# STM32WL_QFN48_4Layers_Ref_Board.net
KiCad netlist of a schematic drawn in Altium Designer
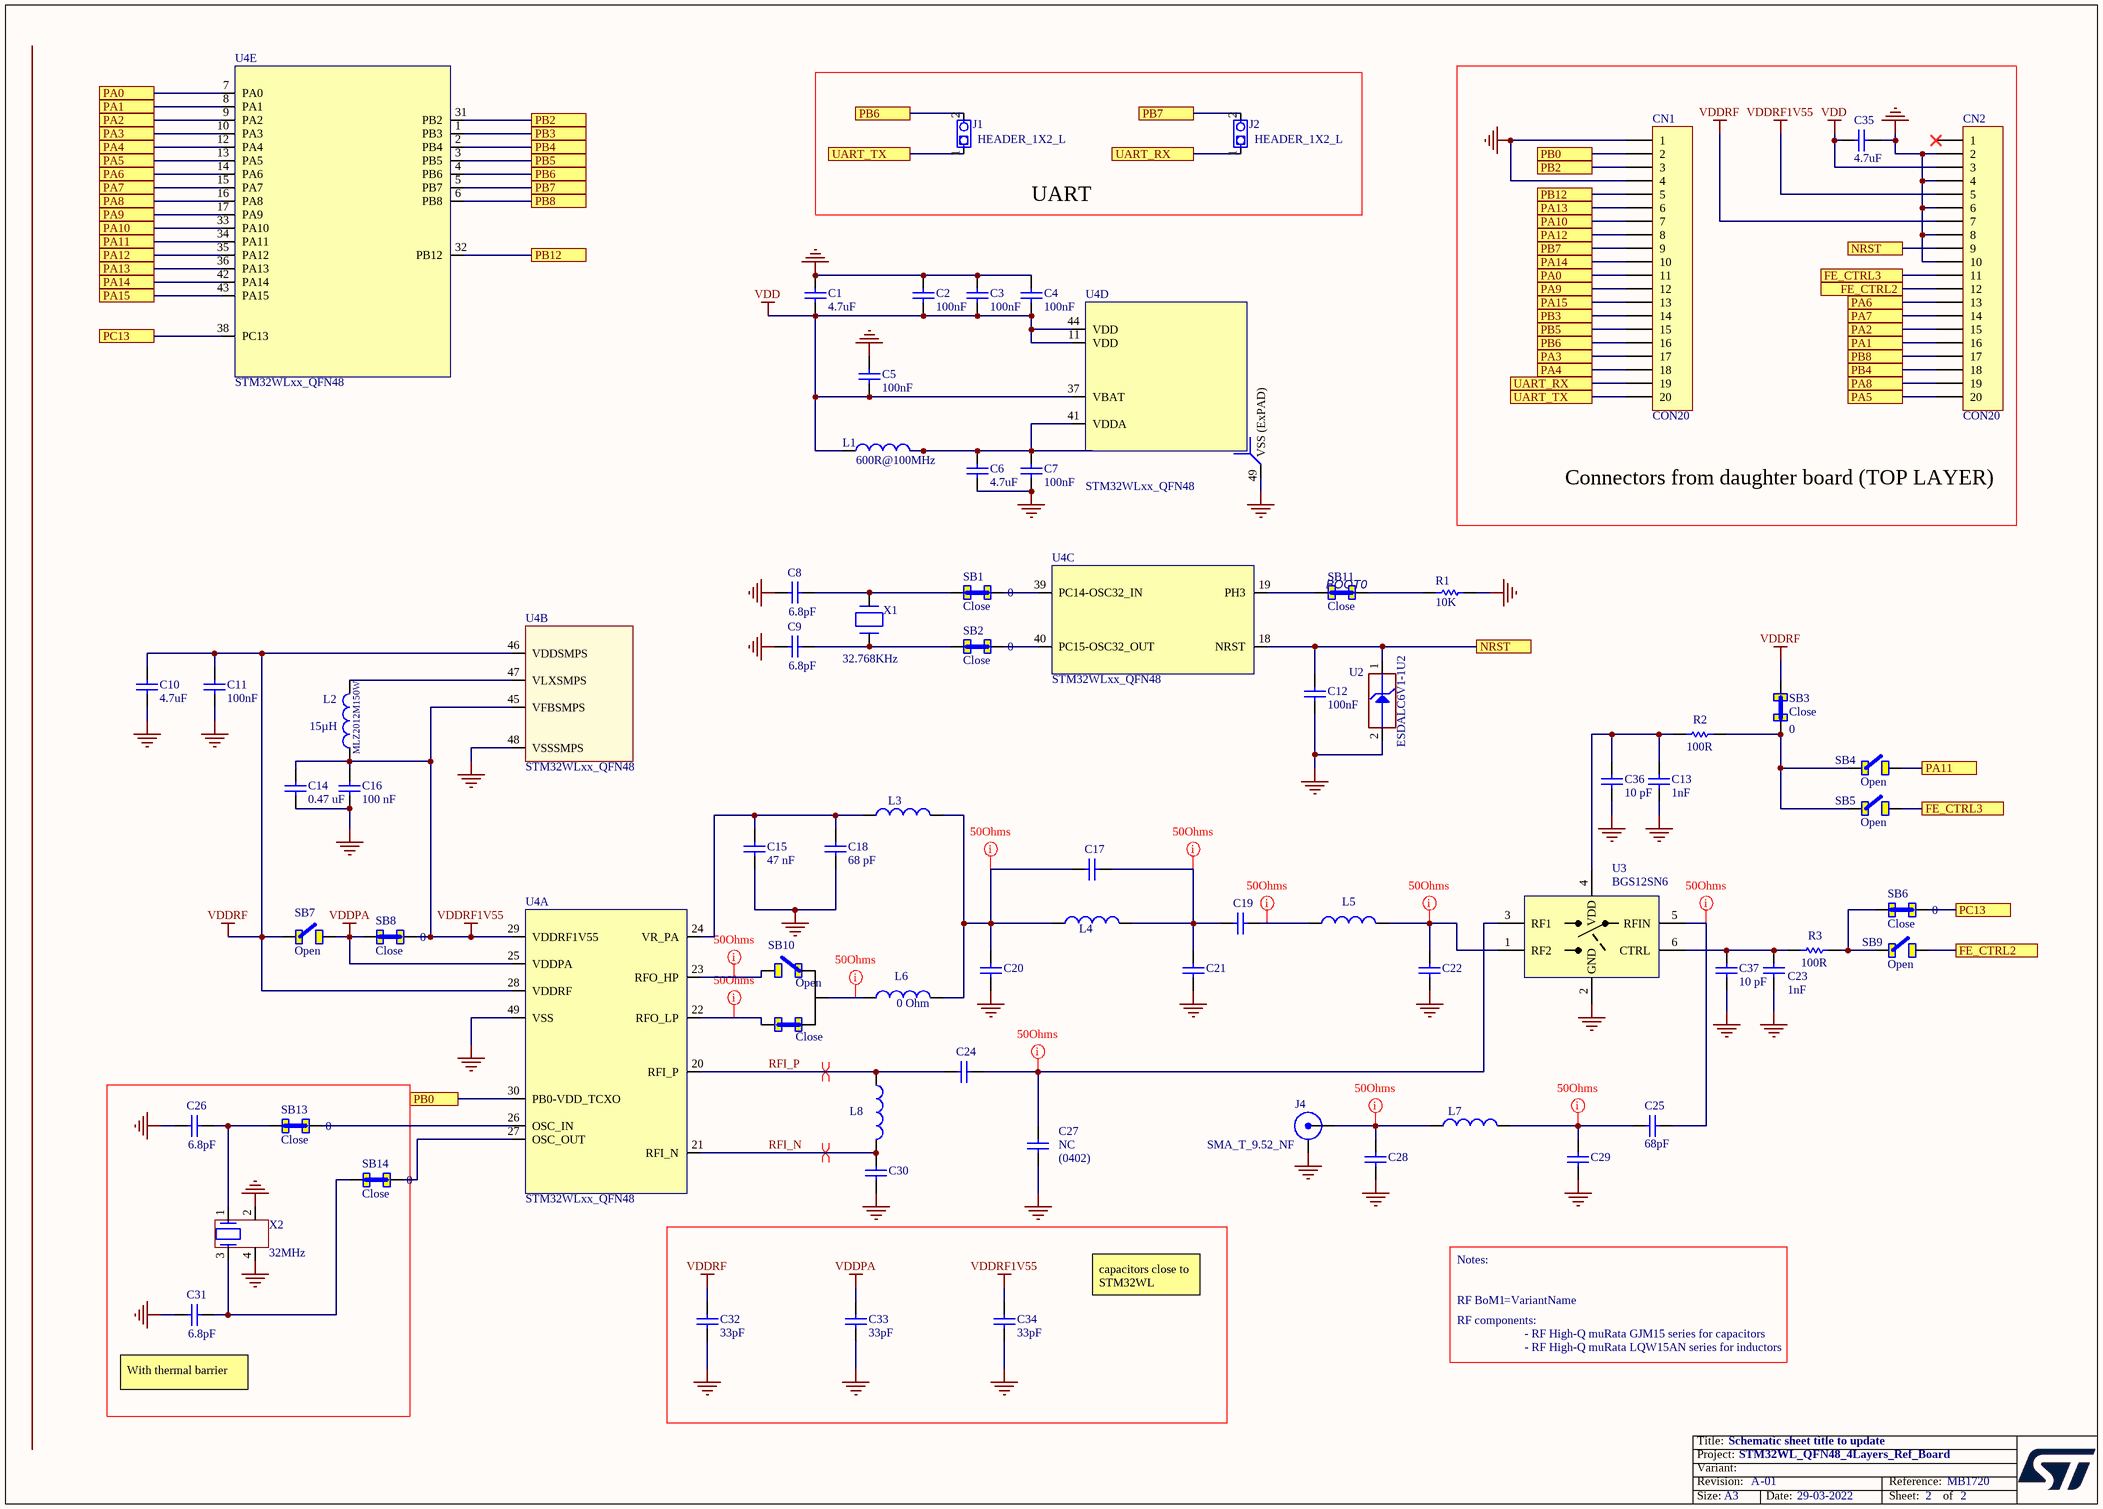
[diagram p0: STM32WL_QFN48_4Layers_Ref_Board.SchDoc]

(export (version "E")
  (design (tool "Eeschema 10.0.6"))
  (components
    (comp (ref "C1")
      (value "4.7uF")
      (footprint "CAPC1608X09N")
      (description "Capacitor, MLCC, 4.7uF, 16V, X5R, 10%, 0603, T=0.8mm")
      (fields
        (field (name "MANUFACTURER_PART_NUMBER") "CC0603KRX5R7BB475")
        (field (name "MANUFACTURER") "YAGEO")
      )
      (libsource (lib "MCD_PARTS_database") (part "Capacitor"))
    )
    (comp (ref "C2")
      (value "100nF")
      (footprint "CAPC1005X06N")
      (description "Capacitor, MLCC, 100nF, 16V, X7R, 10%, 0402, T=0,5mm")
      (fields
        (field (name "MANUFACTURER_PART_NUMBER") "CC0402KRX7R7BB104")
        (field (name "MANUFACTURER") "YAGEO")
      )
      (libsource (lib "MCD_PARTS_database") (part "Capacitor"))
    )
    (comp (ref "C3")
      (value "100nF")
      (footprint "CAPC1005X06N")
      (description "Capacitor, MLCC, 100nF, 16V, X7R, 10%, 0402, T=0,5mm")
      (fields
        (field (name "MANUFACTURER_PART_NUMBER") "CC0402KRX7R7BB104")
        (field (name "MANUFACTURER") "YAGEO")
      )
      (libsource (lib "MCD_PARTS_database") (part "Capacitor"))
    )
    (comp (ref "C4")
      (value "100nF")
      (footprint "CAPC1005X06N")
      (description "Capacitor, MLCC, 100nF, 16V, X7R, 10%, 0402, T=0,5mm")
      (fields
        (field (name "MANUFACTURER_PART_NUMBER") "CC0402KRX7R7BB104")
        (field (name "MANUFACTURER") "YAGEO")
      )
      (libsource (lib "MCD_PARTS_database") (part "Capacitor"))
    )
    (comp (ref "C5")
      (value "100nF")
      (footprint "CAPC1005X06N")
      (description "Capacitor, MLCC, 100nF, 16V, X7R, 10%, 0402, T=0,5mm")
      (fields
        (field (name "MANUFACTURER_PART_NUMBER") "CC0402KRX7R7BB104")
        (field (name "MANUFACTURER") "YAGEO")
      )
      (libsource (lib "MCD_PARTS_database") (part "Capacitor"))
    )
    (comp (ref "C6")
      (value "4.7uF")
      (footprint "CAPC1608X09N")
      (description "Capacitor, MLCC, 4.7uF, 16V, X5R, 10%, 0603, T=0.8mm")
      (fields
        (field (name "MANUFACTURER_PART_NUMBER") "CC0603KRX5R7BB475")
        (field (name "MANUFACTURER") "YAGEO")
      )
      (libsource (lib "MCD_PARTS_database") (part "Capacitor"))
    )
    (comp (ref "C7")
      (value "100nF")
      (footprint "CAPC1005X06N")
      (description "Capacitor, MLCC, 100nF, 16V, X7R, 10%, 0402, T=0,5mm")
      (fields
        (field (name "MANUFACTURER_PART_NUMBER") "CC0402KRX7R7BB104")
        (field (name "MANUFACTURER") "YAGEO")
      )
      (libsource (lib "MCD_PARTS_database") (part "Capacitor"))
    )
    (comp (ref "C8")
      (value "6.8pF")
      (footprint "CAPC1005X06N")
      (description "Capacitor, MLCC, 6.8pF, 50V, NPO, +-0.1pF, 0402, T=0.5mm")
      (fields
        (field (name "MANUFACTURER_PART_NUMBER") "GRM1555C1H6R8BA01")
        (field (name "MANUFACTURER") "MURATA")
      )
      (libsource (lib "MCD_PARTS_database") (part "Capacitor"))
    )
    (comp (ref "C9")
      (value "6.8pF")
      (footprint "CAPC1005X06N")
      (description "Capacitor, MLCC, 6.8pF, 50V, NPO, +-0.1pF, 0402, T=0.5mm")
      (fields
        (field (name "MANUFACTURER_PART_NUMBER") "GRM1555C1H6R8BA01")
        (field (name "MANUFACTURER") "MURATA")
      )
      (libsource (lib "MCD_PARTS_database") (part "Capacitor"))
    )
    (comp (ref "C10")
      (value "4.7uF")
      (footprint "CAPC1608X09N")
      (description "Capacitor, MLCC, 4.7uF, 16V, X5R, 10%, 0603, T=0.8mm")
      (fields
        (field (name "MANUFACTURER_PART_NUMBER") "CC0603KRX5R7BB475")
        (field (name "MANUFACTURER") "YAGEO")
      )
      (libsource (lib "MCD_PARTS_database") (part "Capacitor"))
    )
    (comp (ref "C11")
      (value "100nF")
      (footprint "CAPC1005X06N")
      (description "Capacitor, MLCC, 100nF, 16V, X7R, 10%, 0402, T=0,5mm")
      (fields
        (field (name "MANUFACTURER_PART_NUMBER") "CC0402KRX7R7BB104")
        (field (name "MANUFACTURER") "YAGEO")
      )
      (libsource (lib "MCD_PARTS_database") (part "Capacitor"))
    )
    (comp (ref "C12")
      (value "100nF")
      (footprint "CAPC1005X06N")
      (description "Capacitor, MLCC, 100nF, 16V, X7R, 10%, 0402, T=0,5mm")
      (fields
        (field (name "MANUFACTURER_PART_NUMBER") "CC0402KRX7R7BB104")
        (field (name "MANUFACTURER") "YAGEO")
      )
      (libsource (lib "MCD_PARTS_database") (part "Capacitor"))
    )
    (comp (ref "C13")
      (value "1nF")
      (footprint "CAPC1005X06N")
      (description "Capacitor, MLCC, 1nF, 16V, X7R, 10%, 0402, T=0.5mm")
      (fields
        (field (name "MANUFACTURER_PART_NUMBER") "CC0402KRX7R7BB102")
        (field (name "MANUFACTURER") "YAGEO")
      )
      (libsource (lib "MCD_PARTS_database") (part "Capacitor"))
    )
    (comp (ref "C14")
      (value "0.47 uF")
      (footprint "CAPC1608X09N")
      (description "Capacitor, MLCC, 4.7 uF, 16V, X5R, 10%, 0603, T=0.8mm")
      (fields
        (field (name "MANUFACTURER_PART_NUMBER") "CC0603KRX5R7BB474")
        (field (name "MANUFACTURER") "YAGEO")
      )
      (libsource (lib "MCD_PARTS_database") (part "Capacitor"))
    )
    (comp (ref "C15")
      (value "47 nF")
      (footprint "0402")
      (description "Capacitor, MLCC,47nF, 16V, X7R, 10%, 0402, T=0.5mm")
      (fields
        (field (name "MANUFACTURER_PART_NUMBER") "GCM155R71E473KA55")
        (field (name "MANUFACTURER") "MURATA")
      )
      (libsource (lib "MB1791") (part "Capacitor"))
    )
    (comp (ref "C16")
      (value "100 nF")
      (footprint "CAPC1608X09N")
      (description "Capacitor, MLCC, 100 nF, 16V, X5R, 10%, 0603, T=0.8mm")
      (fields (field (name "MANUFACTURER") "YAGEO"))
      (libsource (lib "MCD_PARTS_database") (part "Capacitor"))
    )
    (comp (ref "C17")
      (value "~")
      (footprint "CAPC1005X06N")
      (description "RF Capacitor")
      (libsource (lib "MCD_PARTS_database") (part "Capacitor"))
    )
    (comp (ref "C18")
      (value "68 pF")
      (footprint "0402")
      (description "Capacitor, MLCC,68pF, 50V, C0G, 1%, 0402, T=0.5mm")
      (fields
        (field (name "MANUFACTURER_PART_NUMBER") "GCM1555C1H680JA16")
        (field (name "MANUFACTURER") "MURATA")
      )
      (libsource (lib "MB1791") (part "Capacitor"))
    )
    (comp (ref "C19")
      (value "~")
      (footprint "CAPC1005X06N")
      (description "RF Capacitor")
      (libsource (lib "MCD_PARTS_database") (part "Capacitor"))
    )
    (comp (ref "C20")
      (value "~")
      (footprint "CAPC1005X06N")
      (description "RF Capacitor")
      (fields (field (name "MANUFACTURER_PART_NUMBER") "Not Connected"))
      (libsource (lib "MCD_PARTS_database") (part "Capacitor"))
    )
    (comp (ref "C21")
      (value "~")
      (footprint "CAPC1005X06N")
      (description "RF Capacitor")
      (libsource (lib "MCD_PARTS_database") (part "Capacitor"))
    )
    (comp (ref "C22")
      (value "~")
      (footprint "CAPC1005X06N")
      (description "RF Capacitor")
      (libsource (lib "MCD_PARTS_database") (part "Capacitor"))
    )
    (comp (ref "C23")
      (value "1nF")
      (footprint "CAPC1005X06N")
      (description "Capacitor, MLCC, 1nF, 16V, X7R, 10%, 0402, T=0.5mm")
      (fields
        (field (name "MANUFACTURER_PART_NUMBER") "CC0402KRX7R7BB102")
        (field (name "MANUFACTURER") "YAGEO")
      )
      (libsource (lib "MCD_PARTS_database") (part "Capacitor"))
    )
    (comp (ref "C24")
      (value "~")
      (footprint "CAPC1005X06N")
      (description "RF Capacitor")
      (libsource (lib "MCD_PARTS_database") (part "Capacitor"))
    )
    (comp (ref "C25")
      (value "68pF")
      (footprint "CAPC1005X06N")
      (description "RF Capacitor")
      (fields
        (field (name "MANUFACTURER_PART_NUMBER") "GRM1555C1HR68WB01D")
        (field (name "MANUFACTURER") "Murata")
      )
      (libsource (lib "MCD_PARTS_database") (part "Capacitor"))
    )
    (comp (ref "C26")
      (value "6.8pF")
      (footprint "CAPC1005X06N")
      (description "Capacitor, MLCC, 6.8pF, 50V, NPO, +-0.1pF, 0402, T=0.5mm")
      (fields
        (field (name "MANUFACTURER_PART_NUMBER") "GRM1555C1H6R8BA01")
        (field (name "MANUFACTURER") "MURATA")
      )
      (libsource (lib "MCD_PARTS_database") (part "Capacitor"))
    )
    (comp (ref "C27")
      (value "NC")
      (footprint "CAPC1005X06N")
      (description "RF Capacitor")
      (fields (field (name "MANUFACTURER") "MURATA") (field (name "ALTIUM_VALUE") "(0402)"))
      (libsource (lib "MCD_PARTS_database") (part "Capacitor"))
    )
    (comp (ref "C28")
      (value "~")
      (footprint "CAPC1005X06N - duplicate - duplicate")
      (description "RF Capacitor")
      (libsource (lib "MBxx") (part "Capacitor"))
    )
    (comp (ref "C29")
      (value "~")
      (footprint "CAPC1005X06N - duplicate - duplicate")
      (description "RF Capacitor")
      (libsource (lib "MCD_PARTS_database") (part "Capacitor"))
    )
    (comp (ref "C30")
      (value "~")
      (footprint "CAPC1005X06N")
      (description "RF Capacitor")
      (libsource (lib "MCD_PARTS_database") (part "Capacitor"))
    )
    (comp (ref "C31")
      (value "6.8pF")
      (footprint "CAPC1005X06N")
      (description "Capacitor, MLCC, 6.8pF, 50V, NPO, +-0.1pF, 0402, T=0.5mm")
      (fields
        (field (name "MANUFACTURER_PART_NUMBER") "GRM1555C1H6R8BA01")
        (field (name "MANUFACTURER") "MURATA")
      )
      (libsource (lib "MCD_PARTS_database") (part "Capacitor"))
    )
    (comp (ref "C32")
      (value "33pF")
      (footprint "CAPC1005X06N")
      (description "Capacitor, MLCC, 33pF, 50V, NPO, 2%, 0402, T=0,5mm")
      (fields
        (field (name "MANUFACTURER_PART_NUMBER") "GRM1555C1H330GA01")
        (field (name "MANUFACTURER") "MURATA")
      )
      (libsource (lib "MCD_PARTS_database") (part "Capacitor"))
    )
    (comp (ref "C33")
      (value "33pF")
      (footprint "CAPC1005X06N")
      (description "Capacitor, MLCC, 33pF, 50V, NPO, 2%, 0402, T=0,5mm")
      (fields
        (field (name "MANUFACTURER_PART_NUMBER") "GRM1555C1H330GA01")
        (field (name "MANUFACTURER") "MURATA")
      )
      (libsource (lib "MCD_PARTS_database") (part "Capacitor"))
    )
    (comp (ref "C34")
      (value "33pF")
      (footprint "CAPC1005X06N")
      (description "Capacitor, MLCC, 33pF, 50V, NPO, 2%, 0402, T=0,5mm")
      (fields
        (field (name "MANUFACTURER_PART_NUMBER") "GRM1555C1H330GA01")
        (field (name "MANUFACTURER") "MURATA")
      )
      (libsource (lib "MCD_PARTS_database") (part "Capacitor"))
    )
    (comp (ref "C35")
      (value "4.7uF")
      (footprint "CAPC1608X09N")
      (description "Capacitor, MLCC, 4.7uF, 16V, X5R, 10%, 0603, T=0.8mm")
      (fields
        (field (name "MANUFACTURER_PART_NUMBER") "CC0603KRX5R7BB475")
        (field (name "MANUFACTURER") "YAGEO")
      )
      (libsource (lib "MCD_PARTS_database") (part "Capacitor"))
    )
    (comp (ref "C36")
      (value "10 pF")
      (footprint "CAPC1005X06N")
      (description "10pF ±1% 50V Ceramic Capacitor C0G, NP0 0402 (1005 Metric)")
      (fields
        (field (name "MANUFACTURER_PART_NUMBER") "GJM1555C1H100FB01D")
        (field (name "MANUFACTURER") "MURATA")
      )
      (libsource (lib "MB1720") (part "Capa_0402"))
    )
    (comp (ref "C37")
      (value "10 pF")
      (footprint "CAPC1005X06N")
      (description "10pF ±1% 50V Ceramic Capacitor C0G, NP0 0402 (1005 Metric)")
      (fields
        (field (name "MANUFACTURER_PART_NUMBER") "GJM1555C1H100FB01D")
        (field (name "MANUFACTURER") "MURATA")
      )
      (libsource (lib "MB1720") (part "Capa_0402"))
    )
    (comp (ref "CN1")
      (value "CON20")
      (footprint "CO_SAMTEC_TSW-120-07-x-S")
      (description "Connector right-angle, pitch 2.54mm, 20 contacts")
      (fields
        (field (name "MANUFACTURER") "SAMTEC")
        (field (name "MANUFACTURER_PART_NUMBER") "TSW-120-07-L-S")
      )
      (libsource (lib "Connector") (part "CON20"))
    )
    (comp (ref "CN2")
      (value "CON20")
      (footprint "CO_SAMTEC_TSW-120-07-x-S")
      (description "Connector right-angle, pitch 2.54mm, 20 contacts")
      (fields
        (field (name "MANUFACTURER") "SAMTEC")
        (field (name "MANUFACTURER_PART_NUMBER") "TSW-120-07-L-S")
      )
      (libsource (lib "Connector") (part "CON20"))
    )
    (comp (ref "J1")
      (value "HEADER_1X2_L")
      (footprint "CO_MOLEX_22-03-2021")
      (description "Header 1x2 Through hole 2.54mm")
      (fields (field (name "MANUFACTURER") "MOLEX") (field (name "MANUFACTURER_PART_NUMBER") "22-03-2021"))
      (libsource (lib "Connector") (part "HEADER_1X2_L"))
    )
    (comp (ref "J2")
      (value "HEADER_1X2_L")
      (footprint "CO_MOLEX_22-03-2021")
      (description "Header 1x2 Through hole 2.54mm")
      (fields (field (name "MANUFACTURER") "MOLEX") (field (name "MANUFACTURER_PART_NUMBER") "22-03-2021"))
      (libsource (lib "Connector") (part "HEADER_1X2_L"))
    )
    (comp (ref "J4")
      (value "SMA_T_9.52_NF")
      (footprint "CO_SAMTEC_SMA-J-P-ST-EMI")
      (description "SMA Jack, Edge Mount, 50 Ohms")
      (fields
        (field (name "MANUFACTURER") "SAMTEC")
        (field (name "MANUFACTURER_PART_NUMBER") "SMA-J-P-H-ST-EM1")
      )
      (libsource (lib "STM32WB55_DB_CSP100_P") (part "SMA_T_9.52_NF"))
    )
    (comp (ref "L1")
      (value "600R@100MHz")
      (footprint "INDC1608X95N")
      (description "SMD Chip ferrite bead, 600R@100MHz +/-25%, 350mA, 500mohm DC, 0603, T=0.8mm")
      (fields
        (field (name "MANUFACTURER_PART_NUMBER") "FCM1608KF-601T03")
        (field (name "MANUFACTURER") "TAI-TECH")
      )
      (libsource (lib "MCD_PARTS_database") (part "BEAD"))
    )
    (comp (ref "L2")
      (value "15µH")
      (footprint "INDC2012X13N")
      (description "MLZ2012 Multilayer Shielded Inductor 15µH, ±5%")
      (fields (field (name "MANUFACTURER_PART_NUMBER") "MLZ2012M150W") (field (name "MANUFACTURER") "TDK"))
      (libsource (lib "") (part "Inductor_1"))
    )
    (comp (ref "L3")
      (value "~")
      (footprint "IND_MURATA_LQW15A")
      (description "RF Inductor")
      (fields (field (name "MANUFACTURER") "MURATA"))
      (libsource (lib "MCD_PARTS_database") (part "Inductor"))
    )
    (comp (ref "L4")
      (value "~")
      (footprint "IND_MURATA_LQW15A")
      (description "RF Inductor")
      (libsource (lib "") (part "Inductor_1"))
    )
    (comp (ref "L5")
      (value "~")
      (footprint "IND_MURATA_LQW15A")
      (description "RF Inductor")
      (libsource (lib "") (part "Inductor_1"))
    )
    (comp (ref "L6")
      (value "0 Ohm")
      (footprint "IND_MURATA_LQW15A")
      (description "Résistance 0 ohm")
      (fields
        (field (name "MANUFACTURER_PART_NUMBER") "RCS04020000Z0ED")
        (field (name "MANUFACTURER") "Vishay / Dale")
      )
      (libsource (lib "MCD_PARTS_database") (part "Inductor"))
    )
    (comp (ref "L7")
      (value "~")
      (footprint "IND_MURATA_LQW15A")
      (description "RF Inductor")
      (libsource (lib "MCD_PARTS_database") (part "Inductor"))
    )
    (comp (ref "L8")
      (value "~")
      (footprint "IND_MURATA_LQW15A")
      (description "RF Inductor")
      (libsource (lib "") (part "Inductor_1"))
    )
    (comp (ref "R1")
      (value "10K")
      (footprint "RESC1608X05N")
      (description "Resistor,10K,0603,1%,1/10W")
      (fields
        (field (name "MANUFACTURER_PART_NUMBER") "RC0603FR-0710KL")
        (field (name "MANUFACTURER") "YAGEO")
      )
      (libsource (lib "MCD_PARTS_database") (part "Resistor"))
    )
    (comp (ref "R2")
      (value "100R")
      (footprint "RESC1005X04N")
      (description "Resistor,100R,0402,1%,1/16W")
      (fields
        (field (name "MANUFACTURER_PART_NUMBER") "RC0402FR-07100RL")
        (field (name "MANUFACTURER") "YAGEO")
      )
      (libsource (lib "MCD_PARTS_database") (part "Resistor"))
    )
    (comp (ref "R3")
      (value "100R")
      (footprint "RESC1005X04N")
      (description "Resistor,100R,0402,1%,1/16W")
      (fields
        (field (name "MANUFACTURER_PART_NUMBER") "RC0402FR-07100RL")
        (field (name "MANUFACTURER") "YAGEO")
      )
      (libsource (lib "MCD_PARTS_database") (part "Resistor"))
    )
    (comp (ref "RF BoM1") (value "RF-BOM") (libsource (lib "MB1582") (part "RF-BOM")))
    (comp (ref "SB1")
      (value "Close")
      (footprint "SB_0402")
      (description "Solder Bridge 0R [0402] (Populated with 0 Ohm)")
      (fields
        (field (name "MANUFACTURER") "Vishay / Dale")
        (field (name "MANUFACTURER_PART_NUMBER") "RCS04020000Z0ED")
        (field (name "ALTIUM_VALUE") "0")
      )
      (libsource (lib "MBxx") (part "SB_0Ohm"))
    )
    (comp (ref "SB2")
      (value "Close")
      (footprint "SB_0402")
      (description "Solder Bridge 0R [0402] (Populated with 0 Ohm)")
      (fields
        (field (name "MANUFACTURER") "Vishay / Dale")
        (field (name "MANUFACTURER_PART_NUMBER") "RCS04020000Z0ED")
        (field (name "ALTIUM_VALUE") "0")
      )
      (libsource (lib "MBxx") (part "SB_0Ohm"))
    )
    (comp (ref "SB3")
      (value "Close")
      (footprint "SB_0402")
      (description "Solder Bridge 0R [0402] (Populated with 0 Ohm)")
      (fields
        (field (name "MANUFACTURER") "Vishay / Dale")
        (field (name "MANUFACTURER_PART_NUMBER") "RCS04020000Z0ED")
        (field (name "ALTIUM_VALUE") "0")
      )
      (libsource (lib "MBxx") (part "SB_0Ohm"))
    )
    (comp (ref "SB4")
      (value "Open")
      (footprint "SB_0402")
      (description "Solder Bridge Open [0402] (Unpopulated)")
      (libsource (lib "MBxx") (part "SB_Open"))
    )
    (comp (ref "SB5")
      (value "Open")
      (footprint "SB_0402")
      (description "Solder Bridge Open [0402] (Unpopulated)")
      (libsource (lib "MBxx") (part "SB_Open"))
    )
    (comp (ref "SB6")
      (value "Close")
      (footprint "SB_0402")
      (description "Solder Bridge 0R [0402] (Populated with 0 Ohm)")
      (fields
        (field (name "MANUFACTURER") "Vishay / Dale")
        (field (name "MANUFACTURER_PART_NUMBER") "RCS04020000Z0ED")
        (field (name "ALTIUM_VALUE") "0")
      )
      (libsource (lib "MBxx") (part "SB_0Ohm"))
    )
    (comp (ref "SB7")
      (value "Open")
      (footprint "SB_0402")
      (description "Solder Bridge Open [0402] (Unpopulated)")
      (libsource (lib "MBxx") (part "SB_Open"))
    )
    (comp (ref "SB8")
      (value "Close")
      (footprint "SB_0402")
      (description "Solder Bridge 0R [0402] (Populated with 0 Ohm)")
      (fields
        (field (name "MANUFACTURER") "Vishay / Dale")
        (field (name "MANUFACTURER_PART_NUMBER") "RCS04020000Z0ED")
        (field (name "ALTIUM_VALUE") "0")
      )
      (libsource (lib "MBxx") (part "SB_0Ohm"))
    )
    (comp (ref "SB9")
      (value "Open")
      (footprint "SB_0402")
      (description "Solder Bridge Open [0402] (Unpopulated)")
      (libsource (lib "MBxx") (part "SB_Open"))
    )
    (comp (ref "SB10")
      (value "SB_3Pads")
      (footprint "SB3Pads_0402")
      (description "Solder Bridge")
      (libsource (lib "MBxx") (part "SB_3Pads"))
    )
    (comp (ref "SB11")
      (value "Close")
      (footprint "SB_0402")
      (description "Solder Bridge 0R [0402] (Populated with 0 Ohm)")
      (fields
        (field (name "MANUFACTURER") "Vishay / Dale")
        (field (name "MANUFACTURER_PART_NUMBER") "RCS04020000Z0ED")
      )
      (libsource (lib "MBxx") (part "SB_0Ohm"))
    )
    (comp (ref "SB13")
      (value "Close")
      (footprint "SB_0402")
      (description "Solder Bridge 0R [0402] (Populated with 0 Ohm)")
      (fields
        (field (name "MANUFACTURER") "Vishay / Dale")
        (field (name "MANUFACTURER_PART_NUMBER") "RCS04020000Z0ED")
        (field (name "ALTIUM_VALUE") "0")
      )
      (libsource (lib "MBxx") (part "SB_0Ohm"))
    )
    (comp (ref "SB14")
      (value "Close")
      (footprint "SB_0402")
      (description "Solder Bridge 0R [0402] (Populated with 0 Ohm)")
      (fields
        (field (name "MANUFACTURER") "Vishay / Dale")
        (field (name "MANUFACTURER_PART_NUMBER") "RCS04020000Z0ED")
        (field (name "ALTIUM_VALUE") "0")
      )
      (libsource (lib "MBxx") (part "SB_0Ohm"))
    )
    (comp (ref "U2")
      (value "~")
      (footprint "DIOM0603X03N")
      (description "ESD protection 6V1")
      (fields
        (field (name "MANUFACTURER_PART_NUMBER") "ESDALC6V1-1U2")
        (field (name "MANUFACTURER") "STMICROELECTRONICS")
      )
      (libsource (lib "MCD_PARTS_database") (part "ESD-TRANSIL"))
    )
    (comp (ref "U3")
      (value "BGS12SN6")
      (footprint "SON40P70X40-6N")
      (description "DC switch - Ultra-Low  SPDT analog switch")
      (fields (field (name "MANUFACTURER") "INFINEON"))
      (libsource (lib "BEE_BGA73_Ref_Board") (part "BGS12SN6"))
    )
    (comp (ref "U4")
      (value "STM32WLxx_QFN48")
      (footprint "STM32WLxx_QFN48")
      (description "HQDC : Verified April, 25 2019")
      (libsource (lib "MBxx") (part "STM32WLxx_QFN48"))
    )
    (comp (ref "X1")
      (value "32.768KHz")
      (footprint "OSC_NDK_NX2012SA")
      (description "Crystal 32.768kHz, 6pF, -+20PPM, R=80K, SMD")
      (fields
        (field (name "MANUFACTURER_PART_NUMBER") "NX2012SA 32.768KHz EXS00A-MU00527")
        (field (name "MANUFACTURER") "NDK")
      )
      (libsource (lib "MCD_PARTS_database") (part "XTAL_2_PINS"))
    )
    (comp (ref "X2")
      (value "32MHz")
      (footprint "OSC_NDK_NX2016SA")
      (description "Crystal 32 MHz, 8pF, -+10 PPM, R=60Ω, SMD")
      (fields
        (field (name "MANUFACTURER_PART_NUMBER") "NX2016SA 32MHz EXS00A-CS06465")
        (field (name "MANUFACTURER") "NDK")
      )
      (libsource (lib "MCD_PARTS_database") (part "XTAL_4_PINS"))
    )
  )
  (nets
    (net (code "1") (name "/FE_CTRL2") (class "Default")
      (node (ref "CN2") (pin "12") (pinfunction "12_12") (pintype "passive"))
      (node (ref "SB9") (pin "1") (pinfunction "1_1") (pintype "passive"))
    )
    (net (code "2") (name "/FE_CTRL3") (class "Default")
      (node (ref "CN2") (pin "11") (pinfunction "11_11") (pintype "passive"))
      (node (ref "SB5") (pin "1") (pinfunction "1_1") (pintype "passive"))
    )
    (net (code "3") (name "/NRST") (class "Default")
      (node (ref "C12") (pin "1") (pinfunction "1_1") (pintype "passive"))
      (node (ref "CN2") (pin "9") (pinfunction "9_9") (pintype "passive"))
      (node (ref "U2") (pin "1") (pinfunction "IO1_1") (pintype "passive"))
      (node (ref "U4") (pin "18") (pinfunction "NRST_18") (pintype "passive"))
    )
    (net (code "4") (name "/PA0") (class "Default")
      (node (ref "CN1") (pin "11") (pinfunction "11_11") (pintype "passive"))
      (node (ref "U4") (pin "7") (pinfunction "PA0_7") (pintype "passive"))
    )
    (net (code "5") (name "/PA1") (class "Default")
      (node (ref "CN2") (pin "16") (pinfunction "16_16") (pintype "passive"))
      (node (ref "U4") (pin "8") (pinfunction "PA1_8") (pintype "passive"))
    )
    (net (code "6") (name "/PA2") (class "Default")
      (node (ref "CN2") (pin "15") (pinfunction "15_15") (pintype "passive"))
      (node (ref "U4") (pin "9") (pinfunction "PA2_9") (pintype "passive"))
    )
    (net (code "7") (name "/PA3") (class "Default")
      (node (ref "CN1") (pin "17") (pinfunction "17_17") (pintype "passive"))
      (node (ref "U4") (pin "10") (pinfunction "PA3_10") (pintype "passive"))
    )
    (net (code "8") (name "/PA4") (class "Default")
      (node (ref "CN1") (pin "18") (pinfunction "18_18") (pintype "passive"))
      (node (ref "U4") (pin "12") (pinfunction "PA4_12") (pintype "passive"))
    )
    (net (code "9") (name "/PA5") (class "Default")
      (node (ref "CN2") (pin "20") (pinfunction "20_20") (pintype "passive"))
      (node (ref "U4") (pin "13") (pinfunction "PA5_13") (pintype "passive"))
    )
    (net (code "10") (name "/PA6") (class "Default")
      (node (ref "CN2") (pin "13") (pinfunction "13_13") (pintype "passive"))
      (node (ref "U4") (pin "14") (pinfunction "PA6_14") (pintype "passive"))
    )
    (net (code "11") (name "/PA7") (class "Default")
      (node (ref "CN2") (pin "14") (pinfunction "14_14") (pintype "passive"))
      (node (ref "U4") (pin "15") (pinfunction "PA7_15") (pintype "passive"))
    )
    (net (code "12") (name "/PA8") (class "Default")
      (node (ref "CN2") (pin "19") (pinfunction "19_19") (pintype "passive"))
      (node (ref "U4") (pin "16") (pinfunction "PA8_16") (pintype "passive"))
    )
    (net (code "13") (name "/PA9") (class "Default")
      (node (ref "CN1") (pin "12") (pinfunction "12_12") (pintype "passive"))
      (node (ref "U4") (pin "17") (pinfunction "PA9_17") (pintype "passive"))
    )
    (net (code "14") (name "/PA10") (class "Default")
      (node (ref "CN1") (pin "7") (pinfunction "7_7") (pintype "passive"))
      (node (ref "U4") (pin "33") (pinfunction "PA10_33") (pintype "passive"))
    )
    (net (code "15") (name "/PA11") (class "Default")
      (node (ref "SB4") (pin "1") (pinfunction "1_1") (pintype "passive"))
      (node (ref "U4") (pin "34") (pinfunction "PA11_34") (pintype "passive"))
    )
    (net (code "16") (name "/PA12") (class "Default")
      (node (ref "CN1") (pin "8") (pinfunction "8_8") (pintype "passive"))
      (node (ref "U4") (pin "35") (pinfunction "PA12_35") (pintype "passive"))
    )
    (net (code "17") (name "/PA13") (class "Default")
      (node (ref "CN1") (pin "6") (pinfunction "6_6") (pintype "passive"))
      (node (ref "U4") (pin "36") (pinfunction "PA13_36") (pintype "passive"))
    )
    (net (code "18") (name "/PA14") (class "Default")
      (node (ref "CN1") (pin "10") (pinfunction "10_10") (pintype "passive"))
      (node (ref "U4") (pin "42") (pinfunction "PA14_42") (pintype "passive"))
    )
    (net (code "19") (name "/PA15") (class "Default")
      (node (ref "CN1") (pin "13") (pinfunction "13_13") (pintype "passive"))
      (node (ref "U4") (pin "43") (pinfunction "PA15_43") (pintype "passive"))
    )
    (net (code "20") (name "/PB0") (class "Default")
      (node (ref "CN1") (pin "2") (pinfunction "2_2") (pintype "passive"))
      (node (ref "U4") (pin "30") (pinfunction "PB0-VDD_TCXO_30") (pintype "passive"))
    )
    (net (code "21") (name "/PB2") (class "Default")
      (node (ref "CN1") (pin "3") (pinfunction "3_3") (pintype "passive"))
      (node (ref "U4") (pin "31") (pinfunction "PB2_31") (pintype "passive"))
    )
    (net (code "22") (name "/PB3") (class "Default")
      (node (ref "CN1") (pin "14") (pinfunction "14_14") (pintype "passive"))
      (node (ref "U4") (pin "1") (pinfunction "PB3_1") (pintype "passive"))
    )
    (net (code "23") (name "/PB4") (class "Default")
      (node (ref "CN2") (pin "18") (pinfunction "18_18") (pintype "passive"))
      (node (ref "U4") (pin "2") (pinfunction "PB4_2") (pintype "passive"))
    )
    (net (code "24") (name "/PB5") (class "Default")
      (node (ref "CN1") (pin "15") (pinfunction "15_15") (pintype "passive"))
      (node (ref "U4") (pin "3") (pinfunction "PB5_3") (pintype "passive"))
    )
    (net (code "25") (name "/PB6") (class "Default")
      (node (ref "CN1") (pin "16") (pinfunction "16_16") (pintype "passive"))
      (node (ref "J1") (pin "2") (pinfunction "2_2") (pintype "passive"))
      (node (ref "U4") (pin "4") (pinfunction "PB6_4") (pintype "passive"))
    )
    (net (code "26") (name "/PB7") (class "Default")
      (node (ref "CN1") (pin "9") (pinfunction "9_9") (pintype "passive"))
      (node (ref "J2") (pin "2") (pinfunction "2_2") (pintype "passive"))
      (node (ref "U4") (pin "5") (pinfunction "PB7_5") (pintype "passive"))
    )
    (net (code "27") (name "/PB8") (class "Default")
      (node (ref "CN2") (pin "17") (pinfunction "17_17") (pintype "passive"))
      (node (ref "U4") (pin "6") (pinfunction "PB8_6") (pintype "passive"))
    )
    (net (code "28") (name "/PB12") (class "Default")
      (node (ref "CN1") (pin "5") (pinfunction "5_5") (pintype "passive"))
      (node (ref "U4") (pin "32") (pinfunction "PB12_32") (pintype "passive"))
    )
    (net (code "29") (name "/PC13") (class "Default")
      (node (ref "SB6") (pin "1") (pinfunction "1_1") (pintype "passive"))
      (node (ref "U4") (pin "38") (pinfunction "PC13_38") (pintype "passive"))
    )
    (net (code "30") (name "/RFI_N") (class "Default")
      (node (ref "C30") (pin "2") (pinfunction "2_2") (pintype "passive"))
      (node (ref "L8") (pin "2") (pinfunction "2_2") (pintype "passive"))
      (node (ref "U4") (pin "21") (pinfunction "RFI_N_21") (pintype "passive"))
    )
    (net (code "31") (name "/RFI_P") (class "Default")
      (node (ref "C24") (pin "1") (pinfunction "1_1") (pintype "passive"))
      (node (ref "L8") (pin "1") (pinfunction "1_1") (pintype "passive"))
      (node (ref "U4") (pin "20") (pinfunction "RFI_P_20") (pintype "passive"))
    )
    (net (code "32") (name "/UART_RX") (class "Default")
      (node (ref "CN1") (pin "19") (pinfunction "19_19") (pintype "passive"))
      (node (ref "J2") (pin "1") (pinfunction "1_1") (pintype "passive"))
    )
    (net (code "33") (name "/UART_TX") (class "Default")
      (node (ref "CN1") (pin "20") (pinfunction "20_20") (pintype "passive"))
      (node (ref "J1") (pin "1") (pinfunction "1_1") (pintype "passive"))
    )
    (net (code "34") (name "GND") (class "Default")
      (node (ref "C1") (pin "1") (pinfunction "1_1") (pintype "passive"))
      (node (ref "C10") (pin "2") (pinfunction "2_2") (pintype "passive"))
      (node (ref "C11") (pin "2") (pinfunction "2_2") (pintype "passive"))
      (node (ref "C12") (pin "2") (pinfunction "2_2") (pintype "passive"))
      (node (ref "C13") (pin "1") (pinfunction "1_1") (pintype "passive"))
      (node (ref "C14") (pin "2") (pinfunction "2_2") (pintype "passive"))
      (node (ref "C15") (pin "2") (pinfunction "2_2") (pintype "passive"))
      (node (ref "C16") (pin "2") (pinfunction "2_2") (pintype "passive"))
      (node (ref "C18") (pin "1") (pinfunction "1_1") (pintype "passive"))
      (node (ref "C2") (pin "1") (pinfunction "1_1") (pintype "passive"))
      (node (ref "C20") (pin "2") (pinfunction "2_2") (pintype "passive"))
      (node (ref "C21") (pin "1") (pinfunction "1_1") (pintype "passive"))
      (node (ref "C22") (pin "1") (pinfunction "1_1") (pintype "passive"))
      (node (ref "C23") (pin "1") (pinfunction "1_1") (pintype "passive"))
      (node (ref "C26") (pin "2") (pinfunction "2_2") (pintype "passive"))
      (node (ref "C27") (pin "1") (pinfunction "1_1") (pintype "passive"))
      (node (ref "C28") (pin "2") (pinfunction "2_2") (pintype "passive"))
      (node (ref "C29") (pin "2") (pinfunction "2_2") (pintype "passive"))
      (node (ref "C3") (pin "1") (pinfunction "1_1") (pintype "passive"))
      (node (ref "C30") (pin "1") (pinfunction "1_1") (pintype "passive"))
      (node (ref "C31") (pin "2") (pinfunction "2_2") (pintype "passive"))
      (node (ref "C32") (pin "1") (pinfunction "1_1") (pintype "passive"))
      (node (ref "C33") (pin "1") (pinfunction "1_1") (pintype "passive"))
      (node (ref "C34") (pin "1") (pinfunction "1_1") (pintype "passive"))
      (node (ref "C35") (pin "2") (pinfunction "2_2") (pintype "passive"))
      (node (ref "C36") (pin "1") (pinfunction "1_1") (pintype "passive"))
      (node (ref "C37") (pin "1") (pinfunction "1_1") (pintype "passive"))
      (node (ref "C4") (pin "1") (pinfunction "1_1") (pintype "passive"))
      (node (ref "C5") (pin "1") (pinfunction "1_1") (pintype "passive"))
      (node (ref "C6") (pin "2") (pinfunction "2_2") (pintype "passive"))
      (node (ref "C7") (pin "2") (pinfunction "2_2") (pintype "passive"))
      (node (ref "C8") (pin "2") (pinfunction "2_2") (pintype "passive"))
      (node (ref "C9") (pin "2") (pinfunction "2_2") (pintype "passive"))
      (node (ref "CN1") (pin "1") (pinfunction "1_1") (pintype "passive"))
      (node (ref "CN1") (pin "4") (pinfunction "4_4") (pintype "passive"))
      (node (ref "CN2") (pin "10") (pinfunction "10_10") (pintype "passive"))
      (node (ref "CN2") (pin "2") (pinfunction "2_2") (pintype "passive"))
      (node (ref "CN2") (pin "4") (pinfunction "4_4") (pintype "passive"))
      (node (ref "CN2") (pin "6") (pinfunction "6_6") (pintype "passive"))
      (node (ref "CN2") (pin "8") (pinfunction "8_8") (pintype "passive"))
      (node (ref "J4") (pin "2") (pinfunction "Y_2") (pintype "passive"))
      (node (ref "R1") (pin "1") (pinfunction "1_1") (pintype "passive"))
      (node (ref "U2") (pin "2") (pinfunction "GND_2") (pintype "passive"))
      (node (ref "U3") (pin "2") (pinfunction "GND_2") (pintype "passive"))
      (node (ref "U4") (pin "48") (pinfunction "VSSSMPS_48") (pintype "passive"))
      (node (ref "U4") (pin "49") (pinfunction "VSS_49") (pintype "passive"))
      (node (ref "X2") (pin "2") (pinfunction "2_2") (pintype "passive"))
      (node (ref "X2") (pin "4") (pinfunction "4_4") (pintype "passive"))
    )
    (net (code "35") (name "Net-(C17-Pad1)") (class "Default")
      (node (ref "C17") (pin "1") (pinfunction "1_1") (pintype "passive"))
      (node (ref "C20") (pin "1") (pinfunction "1_1") (pintype "passive"))
      (node (ref "L3") (pin "1") (pinfunction "1_1") (pintype "passive"))
      (node (ref "L4") (pin "1") (pinfunction "1_1") (pintype "passive"))
      (node (ref "L6") (pin "1") (pinfunction "1_1") (pintype "passive"))
    )
    (net (code "36") (name "Net-(C17-Pad2)") (class "Default")
      (node (ref "C17") (pin "2") (pinfunction "2_2") (pintype "passive"))
      (node (ref "C19") (pin "2") (pinfunction "2_2") (pintype "passive"))
      (node (ref "C21") (pin "2") (pinfunction "2_2") (pintype "passive"))
      (node (ref "L4") (pin "2") (pinfunction "2_2") (pintype "passive"))
    )
    (net (code "37") (name "Net-(C19-Pad1)") (class "Default")
      (node (ref "C19") (pin "1") (pinfunction "1_1") (pintype "passive"))
      (node (ref "L5") (pin "1") (pinfunction "1_1") (pintype "passive"))
    )
    (net (code "38") (name "Net-(C25-Pad2)") (class "Default")
      (node (ref "C25") (pin "2") (pinfunction "2_2") (pintype "passive"))
      (node (ref "C29") (pin "1") (pinfunction "1_1") (pintype "passive"))
      (node (ref "L7") (pin "1") (pinfunction "1_1") (pintype "passive"))
    )
    (net (code "39") (name "Net-(C26-Pad1)") (class "Default")
      (node (ref "C26") (pin "1") (pinfunction "1_1") (pintype "passive"))
      (node (ref "SB13") (pin "2") (pinfunction "2_2") (pintype "passive"))
      (node (ref "X2") (pin "1") (pinfunction "1_1") (pintype "passive"))
    )
    (net (code "40") (name "Net-(C31-Pad1)") (class "Default")
      (node (ref "C31") (pin "1") (pinfunction "1_1") (pintype "passive"))
      (node (ref "SB14") (pin "2") (pinfunction "2_2") (pintype "passive"))
      (node (ref "X2") (pin "3") (pinfunction "3_3") (pintype "passive"))
    )
    (net (code "41") (name "Net-(J4-X)") (class "Default")
      (node (ref "C28") (pin "1") (pinfunction "1_1") (pintype "passive"))
      (node (ref "J4") (pin "1") (pinfunction "X_1") (pintype "passive"))
      (node (ref "L7") (pin "2") (pinfunction "2_2") (pintype "passive"))
    )
    (net (code "42") (name "Net-(L6-Pad2)") (class "Default")
      (node (ref "L6") (pin "2") (pinfunction "2_2") (pintype "passive"))
      (node (ref "SB10") (pin "2") (pinfunction "2_2") (pintype "passive"))
    )
    (net (code "43") (name "Net-(R1-Pad2)") (class "Default")
      (node (ref "R1") (pin "2") (pinfunction "2_2") (pintype "passive"))
      (node (ref "SB11") (pin "1") (pinfunction "1_1") (pintype "passive"))
    )
    (net (code "44") (name "Net-(R2-Pad2)") (class "Default")
      (node (ref "R2") (pin "2") (pinfunction "2_2") (pintype "passive"))
      (node (ref "SB3") (pin "2") (pinfunction "2_2") (pintype "passive"))
      (node (ref "SB4") (pin "2") (pinfunction "2_2") (pintype "passive"))
      (node (ref "SB5") (pin "2") (pinfunction "2_2") (pintype "passive"))
    )
    (net (code "45") (name "Net-(R3-Pad2)") (class "Default")
      (node (ref "R3") (pin "2") (pinfunction "2_2") (pintype "passive"))
      (node (ref "SB6") (pin "2") (pinfunction "2_2") (pintype "passive"))
      (node (ref "SB9") (pin "2") (pinfunction "2_2") (pintype "passive"))
    )
    (net (code "46") (name "Net-(U3-CTRL)") (class "Default")
      (node (ref "C23") (pin "2") (pinfunction "2_2") (pintype "passive"))
      (node (ref "C37") (pin "2") (pinfunction "2_2") (pintype "passive"))
      (node (ref "R3") (pin "1") (pinfunction "1_1") (pintype "passive"))
      (node (ref "U3") (pin "6") (pinfunction "CTRL_6") (pintype "passive"))
    )
    (net (code "47") (name "Net-(U3-RF1)") (class "Default")
      (node (ref "C24") (pin "2") (pinfunction "2_2") (pintype "passive"))
      (node (ref "C27") (pin "2") (pinfunction "2_2") (pintype "passive"))
      (node (ref "U3") (pin "3") (pinfunction "RF1_3") (pintype "passive"))
    )
    (net (code "48") (name "Net-(U3-RF2)") (class "Default")
      (node (ref "C22") (pin "2") (pinfunction "2_2") (pintype "passive"))
      (node (ref "L5") (pin "2") (pinfunction "2_2") (pintype "passive"))
      (node (ref "U3") (pin "1") (pinfunction "RF2_1") (pintype "passive"))
    )
    (net (code "49") (name "Net-(U3-RFIN)") (class "Default")
      (node (ref "C25") (pin "1") (pinfunction "1_1") (pintype "passive"))
      (node (ref "U3") (pin "5") (pinfunction "RFIN_5") (pintype "passive"))
    )
    (net (code "50") (name "Net-(U3-VDD)") (class "Default")
      (node (ref "C13") (pin "2") (pinfunction "2_2") (pintype "passive"))
      (node (ref "C36") (pin "2") (pinfunction "2_2") (pintype "passive"))
      (node (ref "R2") (pin "1") (pinfunction "1_1") (pintype "passive"))
      (node (ref "U3") (pin "4") (pinfunction "VDD_4") (pintype "passive"))
    )
    (net (code "51") (name "Net-(U4A-OSC_IN)") (class "Default")
      (node (ref "SB13") (pin "1") (pinfunction "1_1") (pintype "passive"))
      (node (ref "U4") (pin "26") (pinfunction "OSC_IN_26") (pintype "passive"))
    )
    (net (code "52") (name "Net-(U4A-OSC_OUT)") (class "Default")
      (node (ref "SB14") (pin "1") (pinfunction "1_1") (pintype "passive"))
      (node (ref "U4") (pin "27") (pinfunction "OSC_OUT_27") (pintype "passive"))
    )
    (net (code "53") (name "Net-(U4A-RFO_HP)") (class "Default")
      (node (ref "SB10") (pin "1") (pinfunction "1_1") (pintype "passive"))
      (node (ref "U4") (pin "23") (pinfunction "RFO_HP_23") (pintype "passive"))
    )
    (net (code "54") (name "Net-(U4A-RFO_LP)") (class "Default")
      (node (ref "SB10") (pin "3") (pinfunction "3_3") (pintype "passive"))
      (node (ref "U4") (pin "22") (pinfunction "RFO_LP_22") (pintype "passive"))
    )
    (net (code "55") (name "Net-(U4A-VR_PA)") (class "Default")
      (node (ref "C15") (pin "1") (pinfunction "1_1") (pintype "passive"))
      (node (ref "C18") (pin "2") (pinfunction "2_2") (pintype "passive"))
      (node (ref "L3") (pin "2") (pinfunction "2_2") (pintype "passive"))
      (node (ref "U4") (pin "24") (pinfunction "VR_PA_24") (pintype "passive"))
    )
    (net (code "56") (name "Net-(U4B-VLXSMPS)") (class "Default")
      (node (ref "L2") (pin "2") (pinfunction "2_2") (pintype "passive"))
      (node (ref "U4") (pin "47") (pinfunction "VLXSMPS_47") (pintype "passive"))
    )
    (net (code "57") (name "Net-(U4C-PC14-OSC32_IN)") (class "Default")
      (node (ref "SB1") (pin "1") (pinfunction "1_1") (pintype "passive"))
      (node (ref "U4") (pin "39") (pinfunction "PC14-OSC32_IN_39") (pintype "passive"))
    )
    (net (code "58") (name "Net-(U4C-PC15-OSC32_OUT)") (class "Default")
      (node (ref "SB2") (pin "1") (pinfunction "1_1") (pintype "passive"))
      (node (ref "U4") (pin "40") (pinfunction "PC15-OSC32_OUT_40") (pintype "passive"))
    )
    (net (code "59") (name "Net-(U4C-PH3)") (class "Default")
      (node (ref "SB11") (pin "2") (pinfunction "2_2") (pintype "passive"))
      (node (ref "U4") (pin "19") (pinfunction "PH3_19") (pintype "passive"))
    )
    (net (code "60") (name "Net-(U4D-VDDA)") (class "Default")
      (node (ref "C6") (pin "1") (pinfunction "1_1") (pintype "passive"))
      (node (ref "C7") (pin "1") (pinfunction "1_1") (pintype "passive"))
      (node (ref "L1") (pin "2") (pinfunction "2_2") (pintype "passive"))
      (node (ref "U4") (pin "41") (pinfunction "VDDA_41") (pintype "passive"))
    )
    (net (code "61") (name "Net-(X1-X1)") (class "Default")
      (node (ref "C9") (pin "1") (pinfunction "1_1") (pintype "passive"))
      (node (ref "SB2") (pin "2") (pinfunction "2_2") (pintype "passive"))
      (node (ref "X1") (pin "1") (pinfunction "X1_1") (pintype "passive"))
    )
    (net (code "62") (name "Net-(X1-X2)") (class "Default")
      (node (ref "C8") (pin "1") (pinfunction "1_1") (pintype "passive"))
      (node (ref "SB1") (pin "2") (pinfunction "2_2") (pintype "passive"))
      (node (ref "X1") (pin "2") (pinfunction "X2_2") (pintype "passive"))
    )
    (net (code "63") (name "VDD") (class "Default")
      (node (ref "C1") (pin "2") (pinfunction "2_2") (pintype "passive"))
      (node (ref "C2") (pin "2") (pinfunction "2_2") (pintype "passive"))
      (node (ref "C3") (pin "2") (pinfunction "2_2") (pintype "passive"))
      (node (ref "C35") (pin "1") (pinfunction "1_1") (pintype "passive"))
      (node (ref "C4") (pin "2") (pinfunction "2_2") (pintype "passive"))
      (node (ref "C5") (pin "2") (pinfunction "2_2") (pintype "passive"))
      (node (ref "CN2") (pin "3") (pinfunction "3_3") (pintype "passive"))
      (node (ref "L1") (pin "1") (pinfunction "1_1") (pintype "passive"))
      (node (ref "U4") (pin "11") (pinfunction "VDD_11") (pintype "passive"))
      (node (ref "U4") (pin "37") (pinfunction "VBAT_37") (pintype "passive"))
      (node (ref "U4") (pin "44") (pinfunction "VDD_44") (pintype "passive"))
    )
    (net (code "64") (name "VDDPA") (class "Default")
      (node (ref "C33") (pin "2") (pinfunction "2_2") (pintype "passive"))
      (node (ref "SB7") (pin "1") (pinfunction "1_1") (pintype "passive"))
      (node (ref "SB8") (pin "2") (pinfunction "2_2") (pintype "passive"))
      (node (ref "U4") (pin "25") (pinfunction "VDDPA_25") (pintype "passive"))
    )
    (net (code "65") (name "VDDRF") (class "Default")
      (node (ref "C10") (pin "1") (pinfunction "1_1") (pintype "passive"))
      (node (ref "C11") (pin "1") (pinfunction "1_1") (pintype "passive"))
      (node (ref "C32") (pin "2") (pinfunction "2_2") (pintype "passive"))
      (node (ref "CN2") (pin "7") (pinfunction "7_7") (pintype "passive"))
      (node (ref "SB3") (pin "1") (pinfunction "1_1") (pintype "passive"))
      (node (ref "SB7") (pin "2") (pinfunction "2_2") (pintype "passive"))
      (node (ref "U4") (pin "28") (pinfunction "VDDRF_28") (pintype "passive"))
      (node (ref "U4") (pin "46") (pinfunction "VDDSMPS_46") (pintype "passive"))
    )
    (net (code "66") (name "VDDRF1V55") (class "Default")
      (node (ref "C14") (pin "1") (pinfunction "1_1") (pintype "passive"))
      (node (ref "C16") (pin "1") (pinfunction "1_1") (pintype "passive"))
      (node (ref "C34") (pin "2") (pinfunction "2_2") (pintype "passive"))
      (node (ref "CN2") (pin "5") (pinfunction "5_5") (pintype "passive"))
      (node (ref "L2") (pin "1") (pinfunction "1_1") (pintype "passive"))
      (node (ref "SB8") (pin "1") (pinfunction "1_1") (pintype "passive"))
      (node (ref "U4") (pin "29") (pinfunction "VDDRF1V55_29") (pintype "passive"))
      (node (ref "U4") (pin "45") (pinfunction "VFBSMPS_45") (pintype "passive"))
    )
    (net (code "67") (name "unconnected-(CN2-Pad1)") (class "Default")
      (node (ref "CN2") (pin "1") (pinfunction "1_1") (pintype "passive+no_connect"))
    )
  )
)
